# Atmega.net
KiCad netlist of a schematic drawn in Altium Designer
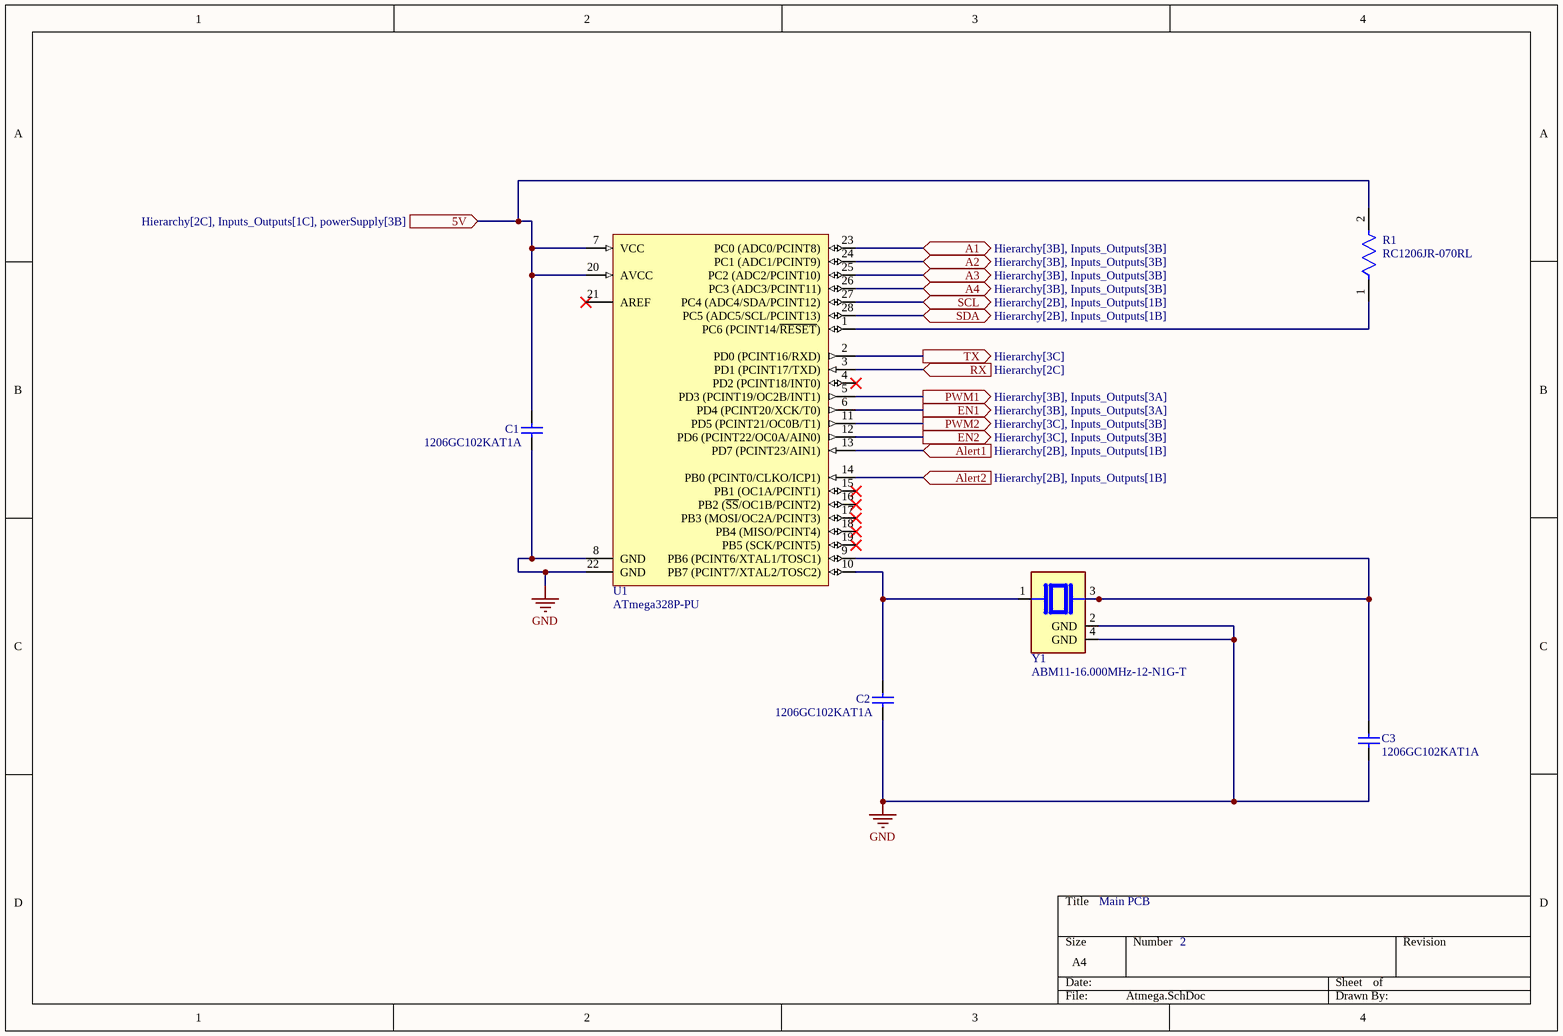
[diagram p0: Atmega.SchDoc]

(export (version "E")
  (design (tool "Eeschema 10.0.6"))
  (components
    (comp (ref "C1")
      (value "1206GC102KAT1A")
      (footprint "AVX-1206-2_L")
      (description "Chip Capacitor, 1 nF, +/- 10%, -55 to 125 degC, 1206 (3216 Metric), RoHS, Tape and Reel")
      (fields (field (name "TOLERANCE") "10%") (field (name "MANUFACTURER") "AVX"))
      (libsource (lib "Altium Content Vault") (part "CAP-NP-2"))
    )
    (comp (ref "C2")
      (value "1206GC102KAT1A")
      (footprint "AVX-1206-2_L")
      (description "Chip Capacitor, 1 nF, +/- 10%, -55 to 125 degC, 1206 (3216 Metric), RoHS, Tape and Reel")
      (fields (field (name "TOLERANCE") "10%") (field (name "MANUFACTURER") "AVX"))
      (libsource (lib "Altium Content Vault") (part "CAP-NP-2"))
    )
    (comp (ref "C3")
      (value "1206GC102KAT1A")
      (footprint "AVX-1206-2_L")
      (description "Chip Capacitor, 1 nF, +/- 10%, -55 to 125 degC, 1206 (3216 Metric), RoHS, Tape and Reel")
      (fields (field (name "TOLERANCE") "10%") (field (name "MANUFACTURER") "AVX"))
      (libsource (lib "Altium Content Vault") (part "CAP-NP-2"))
    )
    (comp (ref "R1")
      (value "RC1206JR-070RL")
      (footprint "FP-RC1206-MFG")
      (description "RES SMD 0 OHM JUMPER 1/4W 1206")
      (fields
        (field (name "MANUFACTURER") "YAGEO")
        (field (name "OCTOPART") "https://octopart.com/rc1206jr-070rl-yageo-40025601")
      )
      (libsource (lib "Altium Content Vault") (part "1029c3af85768c4190bb7ad29bc67b5"))
    )
    (comp (ref "U1")
      (value "ATmega328P-PU")
      (footprint "28P3")
      (libsource (lib "Altium Content Vault") (part "MC-8B-ATM48-IL28"))
    )
    (comp (ref "Y1")
      (value "ABM11-16.000MHz-12-N1G-T")
      (footprint "XTAL_ABM11-16.000MHz-12-N1G-T")
      (fields (field (name "MF") "{'manufacturer': u'Abracon LLC'}"))
      (libsource (lib "ABM11-16.000MHz-12-N1G-T") (part "ABM11-16.000MHz-12-N1G-T"))
    )
  )
  (nets
    (net (code "1") (name "/5V") (class "Default")
      (node (ref "C1") (pin "2") (pinfunction "2_2") (pintype "passive"))
      (node (ref "R1") (pin "2") (pinfunction "2_2") (pintype "passive"))
      (node (ref "U1") (pin "20") (pinfunction "AVCC_20") (pintype "input"))
      (node (ref "U1") (pin "7") (pinfunction "VCC_7") (pintype "input"))
    )
    (net (code "2") (name "/A1") (class "Default")
      (node (ref "U1") (pin "23") (pinfunction "PC0_(ADC0/PCINT8)_23") (pintype "bidirectional"))
    )
    (net (code "3") (name "/A2") (class "Default")
      (node (ref "U1") (pin "24") (pinfunction "PC1_(ADC1/PCINT9)_24") (pintype "bidirectional"))
    )
    (net (code "4") (name "/A3") (class "Default")
      (node (ref "U1") (pin "25") (pinfunction "PC2_(ADC2/PCINT10)_25") (pintype "bidirectional"))
    )
    (net (code "5") (name "/A4") (class "Default")
      (node (ref "U1") (pin "26") (pinfunction "PC3_(ADC3/PCINT11)_26") (pintype "bidirectional"))
    )
    (net (code "6") (name "/Alert1") (class "Default")
      (node (ref "U1") (pin "13") (pinfunction "PD7_(PCINT23/AIN1)_13") (pintype "input"))
    )
    (net (code "7") (name "/Alert2") (class "Default")
      (node (ref "U1") (pin "14") (pinfunction "PB0_(PCINT0/CLKO/ICP1)_14") (pintype "input"))
    )
    (net (code "8") (name "/EN1") (class "Default")
      (node (ref "U1") (pin "6") (pinfunction "PD4_(PCINT20/XCK/T0)_6") (pintype "output"))
    )
    (net (code "9") (name "/EN2") (class "Default")
      (node (ref "U1") (pin "12") (pinfunction "PD6_(PCINT22/OC0A/AIN0)_12") (pintype "output"))
    )
    (net (code "10") (name "/PWM1") (class "Default")
      (node (ref "U1") (pin "5") (pinfunction "PD3_(PCINT19/OC2B/INT1)_5") (pintype "output"))
    )
    (net (code "11") (name "/PWM2") (class "Default")
      (node (ref "U1") (pin "11") (pinfunction "PD5_(PCINT21/OC0B/T1)_11") (pintype "output"))
    )
    (net (code "12") (name "/RX") (class "Default")
      (node (ref "U1") (pin "3") (pinfunction "PD1_(PCINT17/TXD)_3") (pintype "input"))
    )
    (net (code "13") (name "/SCL") (class "Default")
      (node (ref "U1") (pin "27") (pinfunction "PC4_(ADC4/SDA/PCINT12)_27") (pintype "bidirectional"))
    )
    (net (code "14") (name "/SDA") (class "Default")
      (node (ref "U1") (pin "28") (pinfunction "PC5_(ADC5/SCL/PCINT13)_28") (pintype "bidirectional"))
    )
    (net (code "15") (name "/TX") (class "Default")
      (node (ref "U1") (pin "2") (pinfunction "PD0_(PCINT16/RXD)_2") (pintype "output"))
    )
    (net (code "16") (name "GND") (class "Default")
      (node (ref "C1") (pin "1") (pinfunction "1_1") (pintype "passive"))
      (node (ref "C2") (pin "1") (pinfunction "1_1") (pintype "passive"))
      (node (ref "C3") (pin "1") (pinfunction "1_1") (pintype "passive"))
      (node (ref "U1") (pin "22") (pinfunction "GND_22") (pintype "power_in"))
      (node (ref "U1") (pin "8") (pinfunction "GND_8") (pintype "power_in"))
      (node (ref "Y1") (pin "2") (pinfunction "GND_2") (pintype "power_in"))
      (node (ref "Y1") (pin "4") (pinfunction "GND_4") (pintype "power_in"))
    )
    (net (code "17") (name "Net-(U1-PB6_(PCINT6{slash}XTAL1{slash}TOSC1))") (class "Default")
      (node (ref "C3") (pin "2") (pinfunction "2_2") (pintype "passive"))
      (node (ref "U1") (pin "9") (pinfunction "PB6_(PCINT6/XTAL1/TOSC1)_9") (pintype "bidirectional"))
      (node (ref "Y1") (pin "3") (pinfunction "2_3") (pintype "passive"))
    )
    (net (code "18") (name "Net-(U1-PB7_(PCINT7{slash}XTAL2{slash}TOSC2))") (class "Default")
      (node (ref "C2") (pin "2") (pinfunction "2_2") (pintype "passive"))
      (node (ref "U1") (pin "10") (pinfunction "PB7_(PCINT7/XTAL2/TOSC2)_10") (pintype "bidirectional"))
      (node (ref "Y1") (pin "1") (pinfunction "1_1") (pintype "passive"))
    )
    (net (code "19") (name "Net-(U1-PC6_(PCINT14{slash}~{RESET}))") (class "Default")
      (node (ref "R1") (pin "1") (pinfunction "1_1") (pintype "passive"))
      (node (ref "U1") (pin "1") (pinfunction "PC6_(PCINT14/~{RESET})_1") (pintype "bidirectional"))
    )
    (net (code "20") (name "unconnected-(U1-AREF-Pad21)") (class "Default")
      (node (ref "U1") (pin "21") (pinfunction "AREF_21") (pintype "power_in+no_connect"))
    )
    (net (code "21") (name "unconnected-(U1-PB1_(OC1A{slash}PCINT1)-Pad15)") (class "Default")
      (node (ref "U1") (pin "15") (pinfunction "PB1_(OC1A/PCINT1)_15") (pintype "bidirectional+no_connect"))
    )
    (net (code "22") (name "unconnected-(U1-PB2_(~{SS}{slash}OC1B{slash}PCINT2)-Pad16)") (class "Default")
      (node (ref "U1") (pin "16") (pinfunction "PB2_(~{SS}/OC1B/PCINT2)_16") (pintype "bidirectional+no_connect"))
    )
    (net (code "23") (name "unconnected-(U1-PB3_(MOSI{slash}OC2A{slash}PCINT3)-Pad17)") (class "Default")
      (node (ref "U1") (pin "17") (pinfunction "PB3_(MOSI/OC2A/PCINT3)_17") (pintype "bidirectional+no_connect"))
    )
    (net (code "24") (name "unconnected-(U1-PB4_(MISO{slash}PCINT4)-Pad18)") (class "Default")
      (node (ref "U1") (pin "18") (pinfunction "PB4_(MISO/PCINT4)_18") (pintype "bidirectional+no_connect"))
    )
    (net (code "25") (name "unconnected-(U1-PB5_(SCK{slash}PCINT5)-Pad19)") (class "Default")
      (node (ref "U1") (pin "19") (pinfunction "PB5_(SCK/PCINT5)_19") (pintype "bidirectional+no_connect"))
    )
    (net (code "26") (name "unconnected-(U1-PD2_(PCINT18{slash}INT0)-Pad4)") (class "Default")
      (node (ref "U1") (pin "4") (pinfunction "PD2_(PCINT18/INT0)_4") (pintype "bidirectional+no_connect"))
    )
  )
)
